# quadcopter.net
KiCad netlist of a schematic drawn in EAGLE
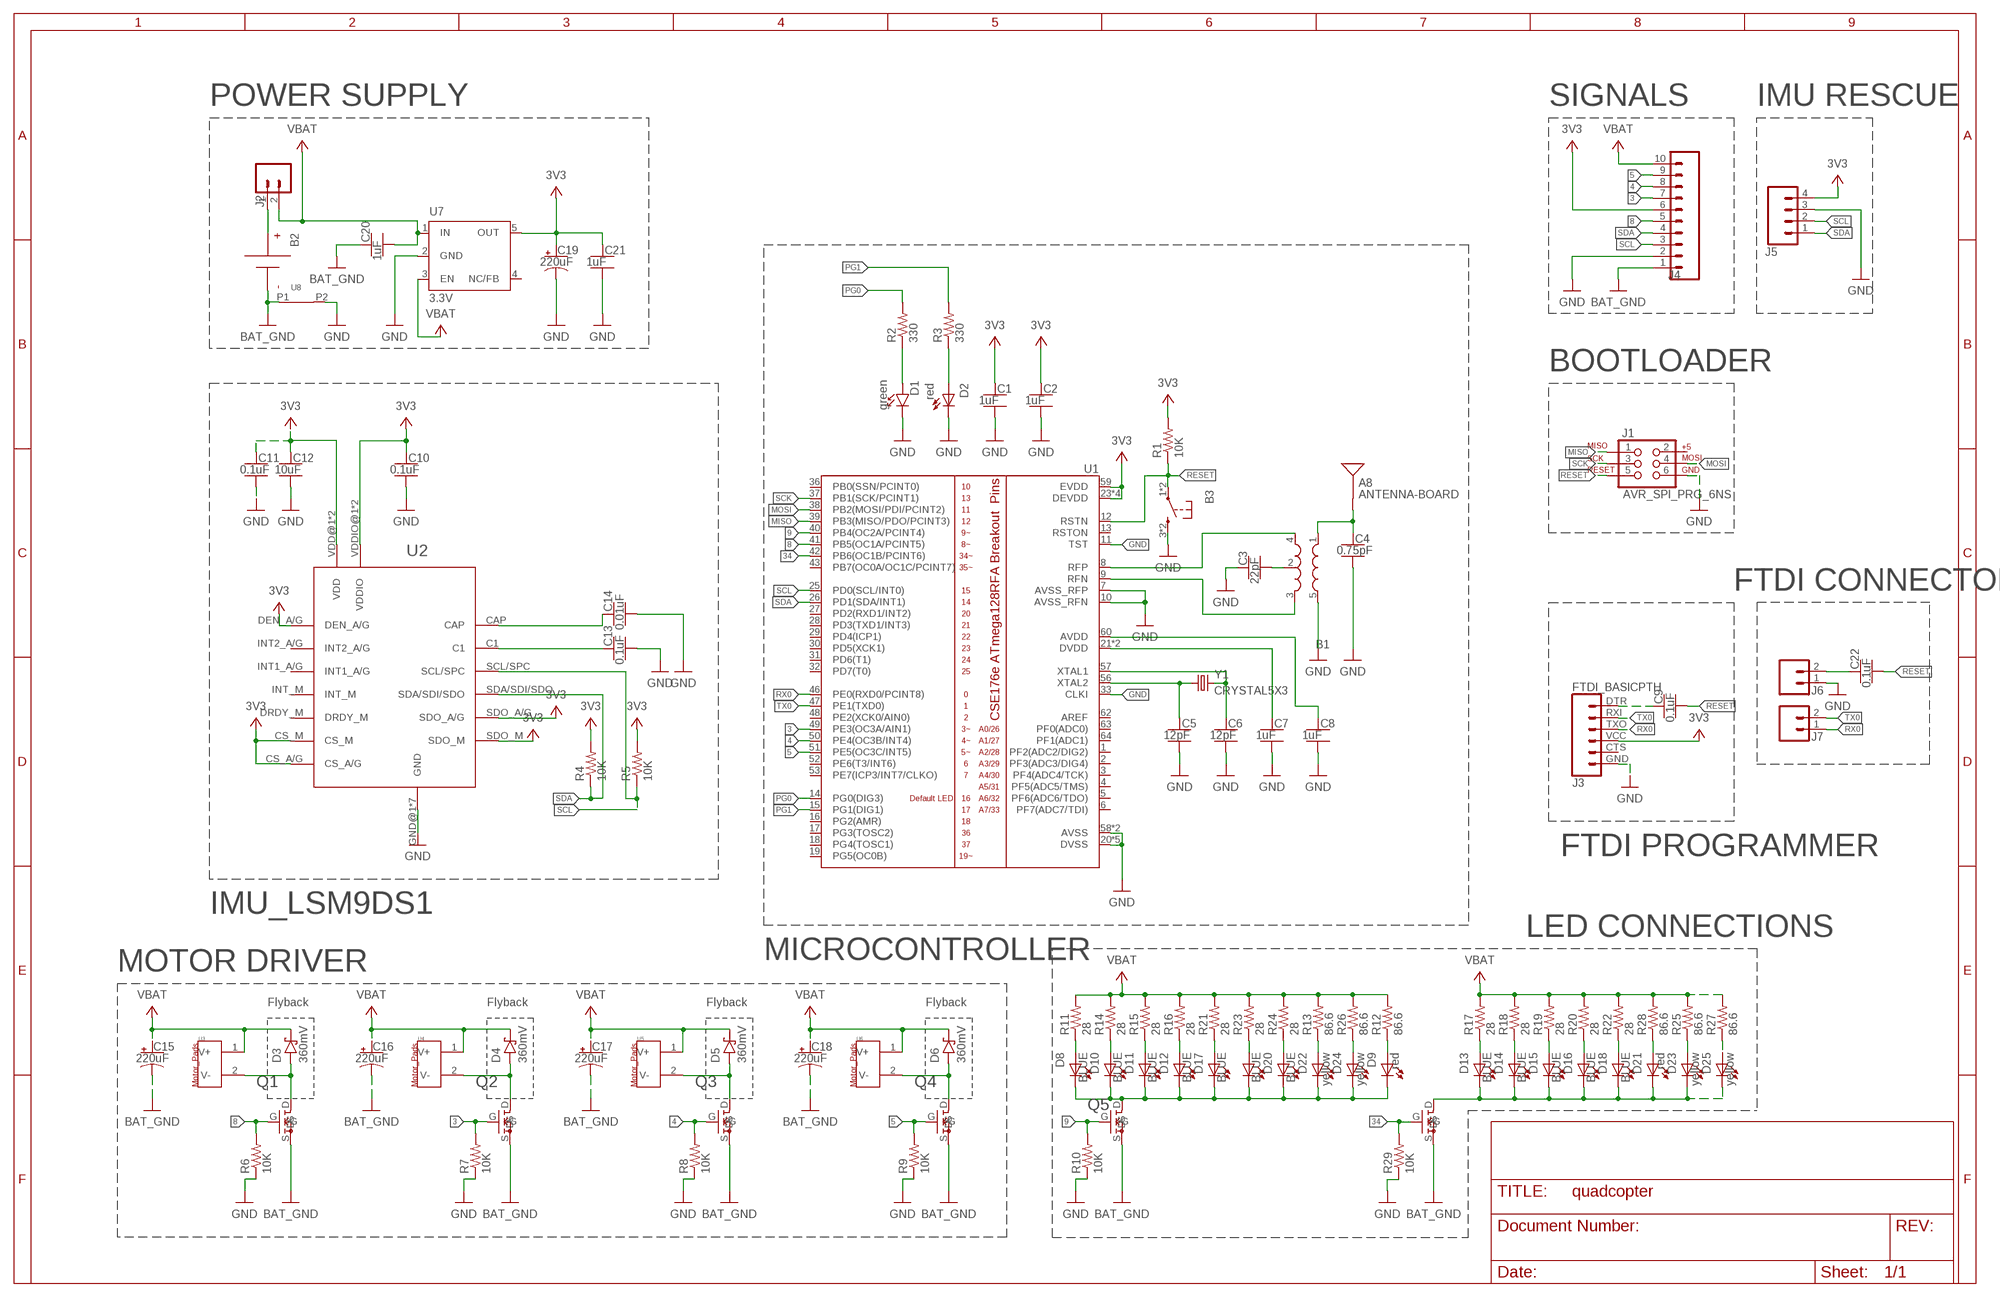
[diagram p0: schematic, sheet 1]

(export (version "E")
  (design (tool "Eeschema 10.0.6"))
  (components
    (comp (ref "A8")
      (value "ANTENNA-BOARD")
      (footprint "eagle-import:ANT_PCB_2.4GHZ_NRF8001_1.6MM_1OZ")
      (libsource (lib "eagle-import") (part "ANTENNA-BOARD"))
    )
    (comp (ref "B1")
      (value "BALUN0805")
      (footprint "eagle-import:BALUN")
      (fields (field (name "MFR") "Wurth Electronics Inc") (field (name "MPN") "748421245"))
      (libsource (lib "eagle-import") (part "BALUN0805"))
    )
    (comp (ref "B2")
      (value "BATTERY-SCREW-TERMINAL")
      (footprint "eagle-import:SCREW-TERMINAL-1X2-2.54MM")
      (libsource (lib "eagle-import") (part "BATTERY-SCREW-TERMINAL"))
    )
    (comp (ref "B3")
      (value "PUSHBUTTON_-4.5X4.5")
      (footprint "eagle-import:4.5MM_TACTILE_SWITCH_TL3305AF160QG")
      (libsource (lib "eagle-import") (part "PUSHBUTTON_-4.5X4.5"))
    )
    (comp (ref "C1")
      (value "1uF")
      (footprint "eagle-import:CAPC2012X140_HS")
      (fields (field (name "MFR") "Taiyo Yuden") (field (name "MPN") "TMK212B7105KG-T"))
      (libsource (lib "eagle-import") (part "CAPACITOR-NP_SMD-2012-0805_CERAMIC-1UF"))
    )
    (comp (ref "C2")
      (value "1uF")
      (footprint "eagle-import:CAPC2012X140_HS")
      (fields (field (name "MFR") "Taiyo Yuden") (field (name "MPN") "TMK212B7105KG-T"))
      (libsource (lib "eagle-import") (part "CAPACITOR-NP_SMD-2012-0805_CERAMIC-1UF"))
    )
    (comp (ref "C3")
      (value "22pF")
      (footprint "eagle-import:CAPC2012X140_HS")
      (fields
        (field (name "MFR") "Murata Electronics North America")
        (field (name "MPN") "GRM21A5C2E220JW01D")
      )
      (libsource (lib "eagle-import") (part "CAPACITOR-NP_SMD-2012-0805_CERAMIC-22PF"))
    )
    (comp (ref "C4")
      (value "0.75pF")
      (footprint "eagle-import:CAPC2012X140_HS")
      (fields
        (field (name "MFR") "Murata Electronics North America")
        (field (name "MPN") "GQM2195C2AR75CB01D")
      )
      (libsource (lib "eagle-import") (part "CAPACITOR-NP_SMD-2012-0805_CERAMIC-0.75PF"))
    )
    (comp (ref "C5")
      (value "12pF")
      (footprint "eagle-import:CAPC2012X140_HS")
      (fields
        (field (name "MFR") "Murata Electronics North America")
        (field (name "MPN") "GRM21A5C2E120JW01D")
      )
      (libsource (lib "eagle-import") (part "CAPACITOR-NP_SMD-2012-0805_CERAMIC-12PF"))
    )
    (comp (ref "C6")
      (value "12pF")
      (footprint "eagle-import:CAPC2012X140_HS")
      (fields
        (field (name "MFR") "Murata Electronics North America")
        (field (name "MPN") "GRM21A5C2E120JW01D")
      )
      (libsource (lib "eagle-import") (part "CAPACITOR-NP_SMD-2012-0805_CERAMIC-12PF"))
    )
    (comp (ref "C7")
      (value "1uF")
      (footprint "eagle-import:CAPC2012X140_HS")
      (fields (field (name "MFR") "Taiyo Yuden") (field (name "MPN") "TMK212B7105KG-T"))
      (libsource (lib "eagle-import") (part "CAPACITOR-NP_SMD-2012-0805_CERAMIC-1UF"))
    )
    (comp (ref "C8")
      (value "1uF")
      (footprint "eagle-import:CAPC2012X140_HS")
      (fields (field (name "MFR") "Taiyo Yuden") (field (name "MPN") "TMK212B7105KG-T"))
      (libsource (lib "eagle-import") (part "CAPACITOR-NP_SMD-2012-0805_CERAMIC-1UF"))
    )
    (comp (ref "C9")
      (value "0.1uF")
      (footprint "eagle-import:CAPC2012X140_HS")
      (fields (field (name "MFR") "TDK") (field (name "MPN") "C2012X7R2A104K125AA"))
      (libsource (lib "eagle-import") (part "CAPACITOR-NP_SMD-2012-0805_CERAMIC-0.1UF"))
    )
    (comp (ref "C10")
      (value "0.1uF")
      (footprint "eagle-import:CAPC2012X140_HS")
      (fields (field (name "MFR") "TDK") (field (name "MPN") "C2012X7R2A104K125AA"))
      (libsource (lib "eagle-import") (part "CAPACITOR-NP_SMD-2012-0805_CERAMIC-0.1UF"))
    )
    (comp (ref "C11")
      (value "0.1uF")
      (footprint "eagle-import:CAPC2012X140_HS")
      (fields (field (name "MFR") "TDK") (field (name "MPN") "C2012X7R2A104K125AA"))
      (libsource (lib "eagle-import") (part "CAPACITOR-NP_SMD-2012-0805_CERAMIC-0.1UF"))
    )
    (comp (ref "C12")
      (value "10uF")
      (footprint "eagle-import:CAPC2012X140_HS")
      (libsource (lib "eagle-import") (part "CAPACITOR-NP_SMD-2012-0805_CERAMIC-10UF"))
    )
    (comp (ref "C13")
      (value "0.1uF")
      (footprint "eagle-import:CAPC2012X140_HS")
      (fields (field (name "MFR") "TDK") (field (name "MPN") "C2012X7R2A104K125AA"))
      (libsource (lib "eagle-import") (part "CAPACITOR-NP_SMD-2012-0805_CERAMIC-0.1UF"))
    )
    (comp (ref "C14")
      (value "0.01uF")
      (footprint "eagle-import:CAPC2012X140_HS")
      (fields (field (name "MFR") "Knowles Syfer") (field (name "MPN") "0805J0500104KJT"))
      (libsource (lib "eagle-import") (part "CAPACITOR-NP_SMD-2012-0805_CERAMIC-0.01UF"))
    )
    (comp (ref "C15")
      (value "220uF")
      (footprint "eagle-import:CAPMP7343X310_HS")
      (fields (field (name "MFR") "AVX Corporation") (field (name "MPN") "TAJD227K006RNJ"))
      (libsource (lib "eagle-import") (part "CAPACITOR-POL_SMD-7043-D_TANTALUM-220UF"))
    )
    (comp (ref "C16")
      (value "220uF")
      (footprint "eagle-import:CAPMP7343X310_HS")
      (fields (field (name "MFR") "AVX Corporation") (field (name "MPN") "TAJD227K006RNJ"))
      (libsource (lib "eagle-import") (part "CAPACITOR-POL_SMD-7043-D_TANTALUM-220UF"))
    )
    (comp (ref "C17")
      (value "220uF")
      (footprint "eagle-import:CAPMP7343X310_HS")
      (fields (field (name "MFR") "AVX Corporation") (field (name "MPN") "TAJD227K006RNJ"))
      (libsource (lib "eagle-import") (part "CAPACITOR-POL_SMD-7043-D_TANTALUM-220UF"))
    )
    (comp (ref "C18")
      (value "220uF")
      (footprint "eagle-import:CAPMP7343X310_HS")
      (fields (field (name "MFR") "AVX Corporation") (field (name "MPN") "TAJD227K006RNJ"))
      (libsource (lib "eagle-import") (part "CAPACITOR-POL_SMD-7043-D_TANTALUM-220UF"))
    )
    (comp (ref "C19")
      (value "220uF")
      (footprint "eagle-import:CAPMP7343X310_HS")
      (fields (field (name "MFR") "AVX Corporation") (field (name "MPN") "TAJD227K006RNJ"))
      (libsource (lib "eagle-import") (part "CAPACITOR-POL_SMD-7043-D_TANTALUM-220UF"))
    )
    (comp (ref "C20")
      (value "1uF")
      (footprint "eagle-import:CAPC2012X140_HS")
      (fields (field (name "MFR") "Taiyo Yuden") (field (name "MPN") "TMK212B7105KG-T"))
      (libsource (lib "eagle-import") (part "CAPACITOR-NP_SMD-2012-0805_CERAMIC-1UF"))
    )
    (comp (ref "C21")
      (value "1uF")
      (footprint "eagle-import:CAPC2012X140_HS")
      (fields (field (name "MFR") "Taiyo Yuden") (field (name "MPN") "TMK212B7105KG-T"))
      (libsource (lib "eagle-import") (part "CAPACITOR-NP_SMD-2012-0805_CERAMIC-1UF"))
    )
    (comp (ref "C22")
      (value "0.1uF")
      (footprint "eagle-import:CAPC2012X140_HS")
      (fields (field (name "MFR") "TDK") (field (name "MPN") "C2012X7R2A104K125AA"))
      (libsource (lib "eagle-import") (part "CAPACITOR-NP_SMD-2012-0805_CERAMIC-0.1UF"))
    )
    (comp (ref "D1")
      (value "green")
      (footprint "eagle-import:LEDSC125X200X120-2_HS")
      (fields (field (name "MFR") "Lite-On Inc") (field (name "MPN") "LTST-C170GKT"))
      (libsource (lib "eagle-import") (part "DIODE-LED_SMD-2012-0805-GREEN"))
    )
    (comp (ref "D2")
      (value "red")
      (footprint "eagle-import:LED")
      (libsource (lib "eagle-import") (part "DIODE-LED-LITEON-C170EKT-RED-LITEON-C170EKT-RED-LED"))
    )
    (comp (ref "D3")
      (value "360mV")
      (footprint "eagle-import:SOD3716X135_HS")
      (fields
        (field (name "MFR") "Toshiba Semiconductor and Storage")
        (field (name "MPN") "CRS08(TE85L,Q,M)")
      )
      (libsource (lib "eagle-import") (part "DIODE-SCHOTTKY_SMD-SOD123-360MV"))
    )
    (comp (ref "D4")
      (value "360mV")
      (footprint "eagle-import:SOD3716X135_HS")
      (fields
        (field (name "MFR") "Toshiba Semiconductor and Storage")
        (field (name "MPN") "CRS08(TE85L,Q,M)")
      )
      (libsource (lib "eagle-import") (part "DIODE-SCHOTTKY_SMD-SOD123-360MV"))
    )
    (comp (ref "D5")
      (value "360mV")
      (footprint "eagle-import:SOD3716X135_HS")
      (fields
        (field (name "MFR") "Toshiba Semiconductor and Storage")
        (field (name "MPN") "CRS08(TE85L,Q,M)")
      )
      (libsource (lib "eagle-import") (part "DIODE-SCHOTTKY_SMD-SOD123-360MV"))
    )
    (comp (ref "D6")
      (value "360mV")
      (footprint "eagle-import:SOD3716X135_HS")
      (fields
        (field (name "MFR") "Toshiba Semiconductor and Storage")
        (field (name "MPN") "CRS08(TE85L,Q,M)")
      )
      (libsource (lib "eagle-import") (part "DIODE-SCHOTTKY_SMD-SOD123-360MV"))
    )
    (comp (ref "D8")
      (value "BLUE")
      (footprint "eagle-import:DIODE-LED-LTST-C170")
      (fields (field (name "MFR") "Lite-On Inc") (field (name "MPN") "LTST-C170TBKT"))
      (libsource (lib "eagle-import") (part "DIODE-LED-SMD-2012-0805-BLUE-BLUE"))
    )
    (comp (ref "D9")
      (value "red")
      (footprint "eagle-import:DIODE-LED-LTST-C170")
      (fields (field (name "MFR") "Lite-on Inc") (field (name "MPN") "LTST-C170KRKT"))
      (libsource (lib "eagle-import") (part "DIODE-LED-SMD-2012-0805-RED-RED"))
    )
    (comp (ref "D10")
      (value "BLUE")
      (footprint "eagle-import:DIODE-LED-LTST-C170")
      (fields (field (name "MFR") "Lite-On Inc") (field (name "MPN") "LTST-C170TBKT"))
      (libsource (lib "eagle-import") (part "DIODE-LED-SMD-2012-0805-BLUE-BLUE"))
    )
    (comp (ref "D11")
      (value "BLUE")
      (footprint "eagle-import:DIODE-LED-LTST-C170")
      (fields (field (name "MFR") "Lite-On Inc") (field (name "MPN") "LTST-C170TBKT"))
      (libsource (lib "eagle-import") (part "DIODE-LED-SMD-2012-0805-BLUE-BLUE"))
    )
    (comp (ref "D12")
      (value "BLUE")
      (footprint "eagle-import:DIODE-LED-LTST-C170")
      (fields (field (name "MFR") "Lite-On Inc") (field (name "MPN") "LTST-C170TBKT"))
      (libsource (lib "eagle-import") (part "DIODE-LED-SMD-2012-0805-BLUE-BLUE"))
    )
    (comp (ref "D13")
      (value "BLUE")
      (footprint "eagle-import:DIODE-LED-LTST-C170")
      (fields (field (name "MFR") "Lite-On Inc") (field (name "MPN") "LTST-C170TBKT"))
      (libsource (lib "eagle-import") (part "DIODE-LED-SMD-2012-0805-BLUE-BLUE"))
    )
    (comp (ref "D14")
      (value "BLUE")
      (footprint "eagle-import:DIODE-LED-LTST-C170")
      (fields (field (name "MFR") "Lite-On Inc") (field (name "MPN") "LTST-C170TBKT"))
      (libsource (lib "eagle-import") (part "DIODE-LED-SMD-2012-0805-BLUE-BLUE"))
    )
    (comp (ref "D15")
      (value "BLUE")
      (footprint "eagle-import:DIODE-LED-LTST-C170")
      (fields (field (name "MFR") "Lite-On Inc") (field (name "MPN") "LTST-C170TBKT"))
      (libsource (lib "eagle-import") (part "DIODE-LED-SMD-2012-0805-BLUE-BLUE"))
    )
    (comp (ref "D16")
      (value "BLUE")
      (footprint "eagle-import:DIODE-LED-LTST-C170")
      (fields (field (name "MFR") "Lite-On Inc") (field (name "MPN") "LTST-C170TBKT"))
      (libsource (lib "eagle-import") (part "DIODE-LED-SMD-2012-0805-BLUE-BLUE"))
    )
    (comp (ref "D17")
      (value "BLUE")
      (footprint "eagle-import:DIODE-LED-LTST-C170")
      (fields (field (name "MFR") "Lite-On Inc") (field (name "MPN") "LTST-C170TBKT"))
      (libsource (lib "eagle-import") (part "DIODE-LED-SMD-2012-0805-BLUE-BLUE"))
    )
    (comp (ref "D18")
      (value "BLUE")
      (footprint "eagle-import:DIODE-LED-LTST-C170")
      (fields (field (name "MFR") "Lite-On Inc") (field (name "MPN") "LTST-C170TBKT"))
      (libsource (lib "eagle-import") (part "DIODE-LED-SMD-2012-0805-BLUE-BLUE"))
    )
    (comp (ref "D19")
      (value "BLUE")
      (footprint "eagle-import:DIODE-LED-LTST-C170")
      (fields (field (name "MFR") "Lite-On Inc") (field (name "MPN") "LTST-C170TBKT"))
      (libsource (lib "eagle-import") (part "DIODE-LED-SMD-2012-0805-BLUE-BLUE"))
    )
    (comp (ref "D20")
      (value "BLUE")
      (footprint "eagle-import:DIODE-LED-LTST-C170")
      (fields (field (name "MFR") "Lite-On Inc") (field (name "MPN") "LTST-C170TBKT"))
      (libsource (lib "eagle-import") (part "DIODE-LED-SMD-2012-0805-BLUE-BLUE"))
    )
    (comp (ref "D21")
      (value "red")
      (footprint "eagle-import:DIODE-LED-LTST-C170")
      (fields (field (name "MFR") "Lite-on Inc") (field (name "MPN") "LTST-C170KRKT"))
      (libsource (lib "eagle-import") (part "DIODE-LED-SMD-2012-0805-RED-RED"))
    )
    (comp (ref "D22")
      (value "yellow")
      (footprint "eagle-import:DIODE-LED-LTST-C170")
      (fields (field (name "MFR") "Lite-On Inc") (field (name "MPN") "LTST-C170KSKT"))
      (libsource (lib "eagle-import") (part "DIODE-LED-SMD-2012-0805-YELLOW-YELLOW"))
    )
    (comp (ref "D23")
      (value "yellow")
      (footprint "eagle-import:DIODE-LED-LTST-C170")
      (fields (field (name "MFR") "Lite-On Inc") (field (name "MPN") "LTST-C170KSKT"))
      (libsource (lib "eagle-import") (part "DIODE-LED-SMD-2012-0805-YELLOW-YELLOW"))
    )
    (comp (ref "D24")
      (value "yellow")
      (footprint "eagle-import:DIODE-LED-LTST-C170")
      (fields (field (name "MFR") "Lite-On Inc") (field (name "MPN") "LTST-C170KSKT"))
      (libsource (lib "eagle-import") (part "DIODE-LED-SMD-2012-0805-YELLOW-YELLOW"))
    )
    (comp (ref "D25")
      (value "yellow")
      (footprint "eagle-import:DIODE-LED-LTST-C170")
      (fields (field (name "MFR") "Lite-On Inc") (field (name "MPN") "LTST-C170KSKT"))
      (libsource (lib "eagle-import") (part "DIODE-LED-SMD-2012-0805-YELLOW-YELLOW"))
    )
    (comp (ref "J1")
      (value "AVR_SPI_PRG_6NS")
      (footprint "eagle-import:2X3-NS")
      (fields (field (name "MFR") "Amphenol FCI") (field (name "MPN") "67997-206HLF"))
      (libsource (lib "eagle-import") (part "AVR_SPI_PRG_6NS"))
    )
    (comp (ref "J2")
      (value "HEADER-0.1IN-2POS-MALE")
      (footprint "eagle-import:HDRV2W63P254_2X1_508X254H838_HS")
      (libsource (lib "eagle-import") (part "HEADER-0.1IN-2POS-MALE"))
    )
    (comp (ref "J3")
      (value "FTDI_BASICPTH")
      (footprint "eagle-import:FTDI_BASIC")
      (fields (field (name "MFR") "Amphenol FCI") (field (name "MPN") "68016-406HLF"))
      (libsource (lib "eagle-import") (part "FTDI_BASICPTH"))
    )
    (comp (ref "J4")
      (value "HEADER-10POSTH-254X10")
      (footprint "eagle-import:HDRV10W63P254_10X1_2540X254H838_HS")
      (fields (field (name "MFR") "Amphenol FCI") (field (name "MPN") "68000-110HLF"))
      (libsource (lib "eagle-import") (part "HEADER-10POSTH-254X10"))
    )
    (comp (ref "J5")
      (value "HEADER-4POS-0.1IN-FEMALE")
      (footprint "eagle-import:HDRVR4W80P254_1X4_1066X254X850B")
      (libsource (lib "eagle-import") (part "HEADER-4POS-0.1IN-FEMALE"))
    )
    (comp (ref "J6")
      (value "HEADER-0.1IN-2POS-FEMALE")
      (footprint "eagle-import:HDRV2W63P254_2X1_508X254H838_HS")
      (libsource (lib "eagle-import") (part "HEADER-0.1IN-2POS-FEMALE"))
    )
    (comp (ref "J7")
      (value "HEADER-0.1IN-2POS-FEMALE")
      (footprint "eagle-import:HDRV2W63P254_2X1_508X254H838_HS")
      (libsource (lib "eagle-import") (part "HEADER-0.1IN-2POS-FEMALE"))
    )
    (comp (ref "Q1")
      (value "MOSFET-VISHAY-SOT23-N-MOSFET")
      (footprint "eagle-import:SOT-23_N_MOSFET")
      (libsource (lib "eagle-import") (part "MOSFET-VISHAY-SOT23-N-MOSFET"))
    )
    (comp (ref "Q2")
      (value "MOSFET-VISHAY-SOT23-N-MOSFET")
      (footprint "eagle-import:SOT-23_N_MOSFET")
      (libsource (lib "eagle-import") (part "MOSFET-VISHAY-SOT23-N-MOSFET"))
    )
    (comp (ref "Q3")
      (value "MOSFET-VISHAY-SOT23-N-MOSFET")
      (footprint "eagle-import:SOT-23_N_MOSFET")
      (libsource (lib "eagle-import") (part "MOSFET-VISHAY-SOT23-N-MOSFET"))
    )
    (comp (ref "Q4")
      (value "MOSFET-VISHAY-SOT23-N-MOSFET")
      (footprint "eagle-import:SOT-23_N_MOSFET")
      (libsource (lib "eagle-import") (part "MOSFET-VISHAY-SOT23-N-MOSFET"))
    )
    (comp (ref "Q5")
      (value "MOSFET-VISHAY-SOT23-N-MOSFET")
      (footprint "eagle-import:SOT-23_N_MOSFET")
      (libsource (lib "eagle-import") (part "MOSFET-VISHAY-SOT23-N-MOSFET"))
    )
    (comp (ref "Q6")
      (value "MOSFET-VISHAY-SOT23-N-MOSFET")
      (footprint "eagle-import:SOT-23_N_MOSFET")
      (libsource (lib "eagle-import") (part "MOSFET-VISHAY-SOT23-N-MOSFET"))
    )
    (comp (ref "R1")
      (value "10K")
      (footprint "eagle-import:RESC2012X60_HS")
      (fields (field (name "MFR") "Yageo") (field (name "MPN") "RC0805JR-0710KL"))
      (libsource (lib "eagle-import") (part "quadparts_prebuilt_RESISTOR_SMD-2012-0805-10K"))
    )
    (comp (ref "R2")
      (value "330")
      (footprint "eagle-import:RESC2012X60_HS")
      (fields (field (name "MFR") "Yageo") (field (name "MPN") "RC0805JR-07330RL"))
      (libsource (lib "eagle-import") (part "quadparts_prebuilt_RESISTOR_SMD-2012-0805-330"))
    )
    (comp (ref "R3")
      (value "330")
      (footprint "eagle-import:RESC2012X60_HS")
      (fields (field (name "MFR") "Yageo") (field (name "MPN") "RC0805JR-07330RL"))
      (libsource (lib "eagle-import") (part "quadparts_prebuilt_RESISTOR_SMD-2012-0805-330"))
    )
    (comp (ref "R4")
      (value "10K")
      (footprint "eagle-import:RESC2012X60_HS")
      (fields (field (name "MFR") "Yageo") (field (name "MPN") "RC0805JR-0710KL"))
      (libsource (lib "eagle-import") (part "quadparts_prebuilt_RESISTOR_SMD-2012-0805-10K"))
    )
    (comp (ref "R5")
      (value "10K")
      (footprint "eagle-import:RESC2012X60_HS")
      (fields (field (name "MFR") "Yageo") (field (name "MPN") "RC0805JR-0710KL"))
      (libsource (lib "eagle-import") (part "quadparts_prebuilt_RESISTOR_SMD-2012-0805-10K"))
    )
    (comp (ref "R6")
      (value "10K")
      (footprint "eagle-import:RESC2012X60_HS")
      (fields (field (name "MFR") "Yageo") (field (name "MPN") "RC0805JR-0710KL"))
      (libsource (lib "eagle-import") (part "quadparts_prebuilt_RESISTOR_SMD-2012-0805-10K"))
    )
    (comp (ref "R7")
      (value "10K")
      (footprint "eagle-import:RESC2012X60_HS")
      (fields (field (name "MFR") "Yageo") (field (name "MPN") "RC0805JR-0710KL"))
      (libsource (lib "eagle-import") (part "quadparts_prebuilt_RESISTOR_SMD-2012-0805-10K"))
    )
    (comp (ref "R8")
      (value "10K")
      (footprint "eagle-import:RESC2012X60_HS")
      (fields (field (name "MFR") "Yageo") (field (name "MPN") "RC0805JR-0710KL"))
      (libsource (lib "eagle-import") (part "quadparts_prebuilt_RESISTOR_SMD-2012-0805-10K"))
    )
    (comp (ref "R9")
      (value "10K")
      (footprint "eagle-import:RESC2012X60_HS")
      (fields (field (name "MFR") "Yageo") (field (name "MPN") "RC0805JR-0710KL"))
      (libsource (lib "eagle-import") (part "quadparts_prebuilt_RESISTOR_SMD-2012-0805-10K"))
    )
    (comp (ref "R10")
      (value "10K")
      (footprint "eagle-import:RESC2012X60_HS")
      (fields (field (name "MFR") "Yageo") (field (name "MPN") "RC0805JR-0710KL"))
      (libsource (lib "eagle-import") (part "quadparts_prebuilt_RESISTOR_SMD-2012-0805-10K"))
    )
    (comp (ref "R11")
      (value "28")
      (footprint "eagle-import:RESC2012X60_HS")
      (libsource (lib "eagle-import") (part "RESISTOR_SMD-2012-0805-28"))
    )
    (comp (ref "R12")
      (value "86.6")
      (footprint "eagle-import:RESC2012X60_HS")
      (libsource (lib "eagle-import") (part "RESISTOR_SMD-2012-0805-88.6"))
    )
    (comp (ref "R13")
      (value "86.6")
      (footprint "eagle-import:RESC2012X60_HS")
      (libsource (lib "eagle-import") (part "RESISTOR_SMD-2012-0805-88.6"))
    )
    (comp (ref "R14")
      (value "28")
      (footprint "eagle-import:RESC2012X60_HS")
      (libsource (lib "eagle-import") (part "RESISTOR_SMD-2012-0805-28"))
    )
    (comp (ref "R15")
      (value "28")
      (footprint "eagle-import:RESC2012X60_HS")
      (libsource (lib "eagle-import") (part "RESISTOR_SMD-2012-0805-28"))
    )
    (comp (ref "R16")
      (value "28")
      (footprint "eagle-import:RESC2012X60_HS")
      (libsource (lib "eagle-import") (part "RESISTOR_SMD-2012-0805-28"))
    )
    (comp (ref "R17")
      (value "28")
      (footprint "eagle-import:RESC2012X60_HS")
      (libsource (lib "eagle-import") (part "RESISTOR_SMD-2012-0805-28"))
    )
    (comp (ref "R18")
      (value "28")
      (footprint "eagle-import:RESC2012X60_HS")
      (libsource (lib "eagle-import") (part "RESISTOR_SMD-2012-0805-28"))
    )
    (comp (ref "R19")
      (value "28")
      (footprint "eagle-import:RESC2012X60_HS")
      (libsource (lib "eagle-import") (part "RESISTOR_SMD-2012-0805-28"))
    )
    (comp (ref "R20")
      (value "28")
      (footprint "eagle-import:RESC2012X60_HS")
      (libsource (lib "eagle-import") (part "RESISTOR_SMD-2012-0805-28"))
    )
    (comp (ref "R21")
      (value "28")
      (footprint "eagle-import:RESC2012X60_HS")
      (libsource (lib "eagle-import") (part "RESISTOR_SMD-2012-0805-28"))
    )
    (comp (ref "R22")
      (value "28")
      (footprint "eagle-import:RESC2012X60_HS")
      (libsource (lib "eagle-import") (part "RESISTOR_SMD-2012-0805-28"))
    )
    (comp (ref "R23")
      (value "28")
      (footprint "eagle-import:RESC2012X60_HS")
      (libsource (lib "eagle-import") (part "RESISTOR_SMD-2012-0805-28"))
    )
    (comp (ref "R24")
      (value "28")
      (footprint "eagle-import:RESC2012X60_HS")
      (libsource (lib "eagle-import") (part "RESISTOR_SMD-2012-0805-28"))
    )
    (comp (ref "R25")
      (value "86.6")
      (footprint "eagle-import:RESC2012X60_HS")
      (libsource (lib "eagle-import") (part "RESISTOR_SMD-2012-0805-88.6"))
    )
    (comp (ref "R26")
      (value "86.6")
      (footprint "eagle-import:RESC2012X60_HS")
      (libsource (lib "eagle-import") (part "RESISTOR_SMD-2012-0805-88.6"))
    )
    (comp (ref "R27")
      (value "86.6")
      (footprint "eagle-import:RESC2012X60_HS")
      (libsource (lib "eagle-import") (part "RESISTOR_SMD-2012-0805-88.6"))
    )
    (comp (ref "R28")
      (value "86.6")
      (footprint "eagle-import:RESC2012X60_HS")
      (libsource (lib "eagle-import") (part "RESISTOR_SMD-2012-0805-88.6"))
    )
    (comp (ref "R29")
      (value "10K")
      (footprint "eagle-import:RESC2012X60_HS")
      (fields (field (name "MFR") "Yageo") (field (name "MPN") "RC0805JR-0710KL"))
      (libsource (lib "eagle-import") (part "quadparts_prebuilt_RESISTOR_SMD-2012-0805-10K"))
    )
    (comp (ref "U1")
      (value "ATMEGA128RFA1")
      (footprint "eagle-import:QFN-64")
      (fields (field (name "MFR") "Atmel") (field (name "MPN") "ATMEGA128RFA1-ZUR00"))
      (libsource (lib "eagle-import") (part "ATMEGA128RFA1"))
    )
    (comp (ref "U2")
      (value "IMU_LSM-ST-LSM9DS1-IMU-LGA")
      (footprint "eagle-import:LSM9DS1_IMU")
      (libsource (lib "eagle-import") (part "IMU_LSM-ST-LSM9DS1-IMU-LGA"))
    )
    (comp (ref "U3")
      (value "MOTOR_PADS-MOLEX-0530470210")
      (footprint "eagle-import:MOLEX-0530470210")
      (libsource (lib "eagle-import") (part "MOTOR_PADS-MOLEX-0530470210"))
    )
    (comp (ref "U4")
      (value "MOTOR_PADS-MOLEX-0530470210")
      (footprint "eagle-import:MOLEX-0530470210")
      (libsource (lib "eagle-import") (part "MOTOR_PADS-MOLEX-0530470210"))
    )
    (comp (ref "U5")
      (value "MOTOR_PADS-MOLEX-0530470210")
      (footprint "eagle-import:MOLEX-0530470210")
      (libsource (lib "eagle-import") (part "MOTOR_PADS-MOLEX-0530470210"))
    )
    (comp (ref "U6")
      (value "MOTOR_PADS-MOLEX-0530470210")
      (footprint "eagle-import:MOLEX-0530470210")
      (libsource (lib "eagle-import") (part "MOTOR_PADS-MOLEX-0530470210"))
    )
    (comp (ref "U7")
      (value "3.3V")
      (footprint "eagle-import:SOT23-DBV")
      (libsource (lib "eagle-import") (part "TPS73633-DBVT3V3"))
    )
    (comp (ref "U8")
      (value "NET_BRIDGE-BRIDGE-SMD")
      (footprint "eagle-import:NET_BRIDGE")
      (libsource (lib "eagle-import") (part "NET_BRIDGE-BRIDGE-SMD"))
    )
    (comp (ref "Y1")
      (value "CRYSTAL5X3")
      (footprint "eagle-import:CRYSTAL-SMD-5X3")
      (fields (field (name "MFR") "Abracon LLC") (field (name "MPN") "ABM3B-16.000MHZ-B2-T"))
      (libsource (lib "eagle-import") (part "CRYSTAL5X3"))
    )
  )
  (nets
    (net (code "1") (name "3") (class "Default")
      (node (ref "J4") (pin "7") (pinfunction "7_7") (pintype "passive"))
      (node (ref "Q2") (pin "G") (pinfunction "G_G") (pintype "bidirectional"))
      (node (ref "R7") (pin "2") (pinfunction "2_2") (pintype "passive"))
      (node (ref "U1") (pin "49") (pinfunction "PE3(OC3A/AIN1)_49") (pintype "bidirectional"))
    )
    (net (code "2") (name "3V3") (class "Default")
      (node (ref "C1") (pin "1") (pinfunction "1_1") (pintype "passive"))
      (node (ref "C10") (pin "1") (pinfunction "1_1") (pintype "passive"))
      (node (ref "C11") (pin "1") (pinfunction "1_1") (pintype "passive"))
      (node (ref "C12") (pin "1") (pinfunction "1_1") (pintype "passive"))
      (node (ref "C19") (pin "1") (pinfunction "+_1") (pintype "passive"))
      (node (ref "C2") (pin "1") (pinfunction "1_1") (pintype "passive"))
      (node (ref "C21") (pin "1") (pinfunction "1_1") (pintype "passive"))
      (node (ref "J3") (pin "VCC") (pinfunction "4_VCC") (pintype "passive"))
      (node (ref "J4") (pin "6") (pinfunction "6_6") (pintype "passive"))
      (node (ref "J5") (pin "4") (pinfunction "4_4") (pintype "bidirectional"))
      (node (ref "R1") (pin "2") (pinfunction "2_2") (pintype "passive"))
      (node (ref "R4") (pin "2") (pinfunction "2_2") (pintype "passive"))
      (node (ref "R5") (pin "2") (pinfunction "2_2") (pintype "passive"))
      (node (ref "U1") (pin "23") (pinfunction "DEVDD_23") (pintype "bidirectional"))
      (node (ref "U1") (pin "34") (pinfunction "DEVDD_34") (pintype "bidirectional"))
      (node (ref "U1") (pin "44") (pinfunction "DEVDD_44") (pintype "bidirectional"))
      (node (ref "U1") (pin "54") (pinfunction "DEVDD_54") (pintype "bidirectional"))
      (node (ref "U1") (pin "59") (pinfunction "EVDD_59") (pintype "bidirectional"))
      (node (ref "U2") (pin "CS_A/G") (pinfunction "CS_A/G_CS_A/G") (pintype "bidirectional"))
      (node (ref "U2") (pin "CS_M") (pinfunction "CS_M_CS_M") (pintype "bidirectional"))
      (node (ref "U2") (pin "DEN_A/G") (pinfunction "DEN_A/G_DEN_A/G") (pintype "bidirectional"))
      (node (ref "U2") (pin "SDO_A/G") (pinfunction "SDO_A/G_SDO_A/G") (pintype "bidirectional"))
      (node (ref "U2") (pin "SDO_M") (pinfunction "SDO_M_SDO_M") (pintype "bidirectional"))
      (node (ref "U2") (pin "VDD@1") (pinfunction "VDD_VDD@1") (pintype "bidirectional"))
      (node (ref "U2") (pin "VDD@2") (pinfunction "VDD_VDD@2") (pintype "bidirectional"))
      (node (ref "U2") (pin "VDDIO@1") (pinfunction "VDDIO_VDDIO@1") (pintype "bidirectional"))
      (node (ref "U2") (pin "VDDIO@2") (pinfunction "VDDIO_VDDIO@2") (pintype "bidirectional"))
      (node (ref "U7") (pin "5") (pinfunction "OUT_5") (pintype "passive"))
    )
    (net (code "3") (name "4") (class "Default")
      (node (ref "J4") (pin "8") (pinfunction "8_8") (pintype "passive"))
      (node (ref "Q3") (pin "G") (pinfunction "G_G") (pintype "bidirectional"))
      (node (ref "R8") (pin "2") (pinfunction "2_2") (pintype "passive"))
      (node (ref "U1") (pin "50") (pinfunction "PE4(OC3B/INT4)_50") (pintype "bidirectional"))
    )
    (net (code "4") (name "5") (class "Default")
      (node (ref "J4") (pin "9") (pinfunction "9_9") (pintype "passive"))
      (node (ref "Q4") (pin "G") (pinfunction "G_G") (pintype "bidirectional"))
      (node (ref "R9") (pin "2") (pinfunction "2_2") (pintype "passive"))
      (node (ref "U1") (pin "51") (pinfunction "PE5(OC3C/INT5)_51") (pintype "bidirectional"))
    )
    (net (code "5") (name "8") (class "Default")
      (node (ref "J4") (pin "5") (pinfunction "5_5") (pintype "passive"))
      (node (ref "Q1") (pin "G") (pinfunction "G_G") (pintype "bidirectional"))
      (node (ref "R6") (pin "2") (pinfunction "2_2") (pintype "passive"))
      (node (ref "U1") (pin "41") (pinfunction "PB5(OC1A/PCINT5)_41") (pintype "bidirectional"))
    )
    (net (code "6") (name "9") (class "Default")
      (node (ref "Q5") (pin "G") (pinfunction "G_G") (pintype "bidirectional"))
      (node (ref "R10") (pin "2") (pinfunction "2_2") (pintype "passive"))
      (node (ref "U1") (pin "40") (pinfunction "PB4(OC2A/PCINT4)_40") (pintype "bidirectional"))
    )
    (net (code "7") (name "34") (class "Default")
      (node (ref "Q6") (pin "G") (pinfunction "G_G") (pintype "bidirectional"))
      (node (ref "R29") (pin "2") (pinfunction "2_2") (pintype "passive"))
      (node (ref "U1") (pin "42") (pinfunction "PB6(OC1B/PCINT6)_42") (pintype "bidirectional"))
    )
    (net (code "8") (name "BAT_GND") (class "Default")
      (node (ref "B2") (pin "1") (pinfunction "N_1") (pintype "bidirectional"))
      (node (ref "C15") (pin "2") (pinfunction "-_2") (pintype "passive"))
      (node (ref "C16") (pin "2") (pinfunction "-_2") (pintype "passive"))
      (node (ref "C17") (pin "2") (pinfunction "-_2") (pintype "passive"))
      (node (ref "C18") (pin "2") (pinfunction "-_2") (pintype "passive"))
      (node (ref "C20") (pin "1") (pinfunction "1_1") (pintype "passive"))
      (node (ref "J4") (pin "1") (pinfunction "1_1") (pintype "passive"))
      (node (ref "Q1") (pin "S") (pinfunction "S_S") (pintype "bidirectional"))
      (node (ref "Q2") (pin "S") (pinfunction "S_S") (pintype "bidirectional"))
      (node (ref "Q3") (pin "S") (pinfunction "S_S") (pintype "bidirectional"))
      (node (ref "Q4") (pin "S") (pinfunction "S_S") (pintype "bidirectional"))
      (node (ref "Q5") (pin "S") (pinfunction "S_S") (pintype "bidirectional"))
      (node (ref "Q6") (pin "S") (pinfunction "S_S") (pintype "bidirectional"))
      (node (ref "U8") (pin "P1") (pinfunction "P1_P1") (pintype "bidirectional"))
    )
    (net (code "9") (name "GND") (class "Default")
      (node (ref "B1") (pin "5") (pinfunction "GND_5") (pintype "bidirectional"))
      (node (ref "B3") (pin "3") (pinfunction "2_3") (pintype "passive"))
      (node (ref "B3") (pin "4") (pinfunction "2_4") (pintype "passive"))
      (node (ref "C1") (pin "2") (pinfunction "2_2") (pintype "passive"))
      (node (ref "C10") (pin "2") (pinfunction "2_2") (pintype "passive"))
      (node (ref "C11") (pin "2") (pinfunction "2_2") (pintype "passive"))
      (node (ref "C12") (pin "2") (pinfunction "2_2") (pintype "passive"))
      (node (ref "C13") (pin "2") (pinfunction "2_2") (pintype "passive"))
      (node (ref "C14") (pin "2") (pinfunction "2_2") (pintype "passive"))
      (node (ref "C19") (pin "2") (pinfunction "-_2") (pintype "passive"))
      (node (ref "C2") (pin "2") (pinfunction "2_2") (pintype "passive"))
      (node (ref "C21") (pin "2") (pinfunction "2_2") (pintype "passive"))
      (node (ref "C3") (pin "1") (pinfunction "1_1") (pintype "passive"))
      (node (ref "C4") (pin "2") (pinfunction "2_2") (pintype "passive"))
      (node (ref "C5") (pin "2") (pinfunction "2_2") (pintype "passive"))
      (node (ref "C6") (pin "2") (pinfunction "2_2") (pintype "passive"))
      (node (ref "C7") (pin "2") (pinfunction "2_2") (pintype "passive"))
      (node (ref "C8") (pin "2") (pinfunction "2_2") (pintype "passive"))
      (node (ref "D1") (pin "C") (pinfunction "C_C") (pintype "passive"))
      (node (ref "D2") (pin "C") (pinfunction "C_C") (pintype "passive"))
      (node (ref "J1") (pin "6") (pinfunction "6_6") (pintype "passive"))
      (node (ref "J3") (pin "GND") (pinfunction "6_GND") (pintype "passive"))
      (node (ref "J4") (pin "2") (pinfunction "2_2") (pintype "passive"))
      (node (ref "J5") (pin "3") (pinfunction "3_3") (pintype "bidirectional"))
      (node (ref "J6") (pin "1") (pinfunction "1_1") (pintype "passive"))
      (node (ref "R10") (pin "1") (pinfunction "1_1") (pintype "passive"))
      (node (ref "R29") (pin "1") (pinfunction "1_1") (pintype "passive"))
      (node (ref "R6") (pin "1") (pinfunction "1_1") (pintype "passive"))
      (node (ref "R7") (pin "1") (pinfunction "1_1") (pintype "passive"))
      (node (ref "R8") (pin "1") (pinfunction "1_1") (pintype "passive"))
      (node (ref "R9") (pin "1") (pinfunction "1_1") (pintype "passive"))
      (node (ref "U1") (pin "10") (pinfunction "AVSS_RFN_10") (pintype "bidirectional"))
      (node (ref "U1") (pin "11") (pinfunction "TST_11") (pintype "bidirectional"))
      (node (ref "U1") (pin "20") (pinfunction "DVSS_20") (pintype "bidirectional"))
      (node (ref "U1") (pin "24") (pinfunction "DVSS_24") (pintype "bidirectional"))
      (node (ref "U1") (pin "33") (pinfunction "CLKI_33") (pintype "bidirectional"))
      (node (ref "U1") (pin "35") (pinfunction "DVSS_35") (pintype "bidirectional"))
      (node (ref "U1") (pin "45") (pinfunction "DVSS_45") (pintype "bidirectional"))
      (node (ref "U1") (pin "55") (pinfunction "DVSS_55") (pintype "bidirectional"))
      (node (ref "U1") (pin "58") (pinfunction "AVSS_58") (pintype "bidirectional"))
      (node (ref "U1") (pin "61") (pinfunction "AVSS_61") (pintype "bidirectional"))
      (node (ref "U1") (pin "7") (pinfunction "AVSS_RFP_7") (pintype "bidirectional"))
      (node (ref "U2") (pin "GND@1") (pinfunction "GND_GND@1") (pintype "bidirectional"))
      (node (ref "U2") (pin "GND@2") (pinfunction "GND_GND@2") (pintype "bidirectional"))
      (node (ref "U2") (pin "RES@1") (pinfunction "GND_RES@1") (pintype "bidirectional"))
      (node (ref "U2") (pin "RES@2") (pinfunction "GND_RES@2") (pintype "bidirectional"))
      (node (ref "U2") (pin "RES@3") (pinfunction "GND_RES@3") (pintype "bidirectional"))
      (node (ref "U2") (pin "RES@4") (pinfunction "GND_RES@4") (pintype "bidirectional"))
      (node (ref "U2") (pin "RES@5") (pinfunction "GND_RES@5") (pintype "bidirectional"))
      (node (ref "U7") (pin "2") (pinfunction "GND_2") (pintype "input"))
      (node (ref "U8") (pin "P2") (pinfunction "P2_P2") (pintype "bidirectional"))
    )
    (net (code "10") (name "MISO") (class "Default")
      (node (ref "J1") (pin "1") (pinfunction "1_1") (pintype "passive"))
      (node (ref "U1") (pin "39") (pinfunction "PB3(MISO/PDO/PCINT3)_39") (pintype "bidirectional"))
    )
    (net (code "11") (name "MOSI") (class "Default")
      (node (ref "J1") (pin "4") (pinfunction "4_4") (pintype "passive"))
      (node (ref "U1") (pin "38") (pinfunction "PB2(MOSI/PDI/PCINT2)_38") (pintype "bidirectional"))
    )
    (net (code "12") (name "Net-(A8-SIGNAL)") (class "Default")
      (node (ref "A8") (pin "FEED") (pinfunction "SIGNAL_FEED") (pintype "bidirectional"))
      (node (ref "B1") (pin "1") (pinfunction "IN_1") (pintype "bidirectional"))
      (node (ref "C4") (pin "1") (pinfunction "1_1") (pintype "passive"))
    )
    (net (code "13") (name "Net-(B1-GND-Pad2)") (class "Default")
      (node (ref "B1") (pin "2") (pinfunction "GND_2") (pintype "bidirectional"))
      (node (ref "C3") (pin "2") (pinfunction "2_2") (pintype "passive"))
    )
    (net (code "14") (name "Net-(B1-OUT1)") (class "Default")
      (node (ref "B1") (pin "4") (pinfunction "OUT1_4") (pintype "bidirectional"))
      (node (ref "U1") (pin "8") (pinfunction "RFP_8") (pintype "bidirectional"))
    )
    (net (code "15") (name "Net-(B1-OUT2)") (class "Default")
      (node (ref "B1") (pin "3") (pinfunction "OUT2_3") (pintype "bidirectional"))
      (node (ref "U1") (pin "9") (pinfunction "RFN_9") (pintype "bidirectional"))
    )
    (net (code "16") (name "Net-(B2-P)") (class "Default")
      (node (ref "B2") (pin "2") (pinfunction "P_2") (pintype "bidirectional"))
      (node (ref "J2") (pin "1") (pinfunction "1_1") (pintype "passive"))
    )
    (net (code "17") (name "Net-(C7-Pad1)") (class "Default")
      (node (ref "C7") (pin "1") (pinfunction "1_1") (pintype "passive"))
      (node (ref "U1") (pin "21") (pinfunction "DVDD_21") (pintype "bidirectional"))
      (node (ref "U1") (pin "22") (pinfunction "DVDD_22") (pintype "bidirectional"))
    )
    (net (code "18") (name "Net-(C13-Pad1)") (class "Default")
      (node (ref "C13") (pin "1") (pinfunction "1_1") (pintype "passive"))
      (node (ref "U2") (pin "C1") (pinfunction "C1_C1") (pintype "bidirectional"))
    )
    (net (code "19") (name "Net-(C14-Pad1)") (class "Default")
      (node (ref "C14") (pin "1") (pinfunction "1_1") (pintype "passive"))
      (node (ref "U2") (pin "CAP") (pinfunction "CAP_CAP") (pintype "bidirectional"))
    )
    (net (code "20") (name "Net-(C22-Pad1)") (class "Default")
      (node (ref "C22") (pin "1") (pinfunction "1_1") (pintype "passive"))
      (node (ref "J6") (pin "2") (pinfunction "2_2") (pintype "passive"))
    )
    (net (code "21") (name "Net-(D1-PadA)") (class "Default")
      (node (ref "D1") (pin "A") (pinfunction "A_A") (pintype "passive"))
      (node (ref "R2") (pin "1") (pinfunction "1_1") (pintype "passive"))
    )
    (net (code "22") (name "Net-(D2-PadA)") (class "Default")
      (node (ref "D2") (pin "A") (pinfunction "A_A") (pintype "passive"))
      (node (ref "R3") (pin "1") (pinfunction "1_1") (pintype "passive"))
    )
    (net (code "23") (name "Net-(D8-PadA)") (class "Default")
      (node (ref "D8") (pin "A") (pinfunction "A_A") (pintype "passive"))
      (node (ref "R11") (pin "1") (pinfunction "1_1") (pintype "passive"))
    )
    (net (code "24") (name "Net-(D9-PadA)") (class "Default")
      (node (ref "D9") (pin "A") (pinfunction "A_A") (pintype "passive"))
      (node (ref "R12") (pin "1") (pinfunction "1_1") (pintype "passive"))
    )
    (net (code "25") (name "Net-(D10-PadA)") (class "Default")
      (node (ref "D10") (pin "A") (pinfunction "A_A") (pintype "passive"))
      (node (ref "R14") (pin "1") (pinfunction "1_1") (pintype "passive"))
    )
    (net (code "26") (name "Net-(D10-PadC)") (class "Default")
      (node (ref "D10") (pin "C") (pinfunction "C_C") (pintype "passive"))
      (node (ref "D11") (pin "C") (pinfunction "C_C") (pintype "passive"))
      (node (ref "D12") (pin "C") (pinfunction "C_C") (pintype "passive"))
      (node (ref "D17") (pin "C") (pinfunction "C_C") (pintype "passive"))
      (node (ref "D19") (pin "C") (pinfunction "C_C") (pintype "passive"))
      (node (ref "D20") (pin "C") (pinfunction "C_C") (pintype "passive"))
      (node (ref "D22") (pin "C") (pinfunction "C_C") (pintype "passive"))
      (node (ref "D24") (pin "C") (pinfunction "C_C") (pintype "passive"))
      (node (ref "D8") (pin "C") (pinfunction "C_C") (pintype "passive"))
      (node (ref "D9") (pin "C") (pinfunction "C_C") (pintype "passive"))
      (node (ref "Q5") (pin "D") (pinfunction "D_D") (pintype "bidirectional"))
    )
    (net (code "27") (name "Net-(D11-PadA)") (class "Default")
      (node (ref "D11") (pin "A") (pinfunction "A_A") (pintype "passive"))
      (node (ref "R15") (pin "1") (pinfunction "1_1") (pintype "passive"))
    )
    (net (code "28") (name "Net-(D12-PadA)") (class "Default")
      (node (ref "D12") (pin "A") (pinfunction "A_A") (pintype "passive"))
      (node (ref "R16") (pin "1") (pinfunction "1_1") (pintype "passive"))
    )
    (net (code "29") (name "Net-(D13-PadA)") (class "Default")
      (node (ref "D13") (pin "A") (pinfunction "A_A") (pintype "passive"))
      (node (ref "R17") (pin "1") (pinfunction "1_1") (pintype "passive"))
    )
    (net (code "30") (name "Net-(D13-PadC)") (class "Default")
      (node (ref "D13") (pin "C") (pinfunction "C_C") (pintype "passive"))
      (node (ref "D14") (pin "C") (pinfunction "C_C") (pintype "passive"))
      (node (ref "D15") (pin "C") (pinfunction "C_C") (pintype "passive"))
      (node (ref "D16") (pin "C") (pinfunction "C_C") (pintype "passive"))
      (node (ref "D18") (pin "C") (pinfunction "C_C") (pintype "passive"))
      (node (ref "D21") (pin "C") (pinfunction "C_C") (pintype "passive"))
      (node (ref "D23") (pin "C") (pinfunction "C_C") (pintype "passive"))
      (node (ref "D25") (pin "C") (pinfunction "C_C") (pintype "passive"))
      (node (ref "Q6") (pin "D") (pinfunction "D_D") (pintype "bidirectional"))
    )
    (net (code "31") (name "Net-(D14-PadA)") (class "Default")
      (node (ref "D14") (pin "A") (pinfunction "A_A") (pintype "passive"))
      (node (ref "R18") (pin "1") (pinfunction "1_1") (pintype "passive"))
    )
    (net (code "32") (name "Net-(D15-PadA)") (class "Default")
      (node (ref "D15") (pin "A") (pinfunction "A_A") (pintype "passive"))
      (node (ref "R19") (pin "1") (pinfunction "1_1") (pintype "passive"))
    )
    (net (code "33") (name "Net-(D16-PadA)") (class "Default")
      (node (ref "D16") (pin "A") (pinfunction "A_A") (pintype "passive"))
      (node (ref "R20") (pin "1") (pinfunction "1_1") (pintype "passive"))
    )
    (net (code "34") (name "Net-(D17-PadA)") (class "Default")
      (node (ref "D17") (pin "A") (pinfunction "A_A") (pintype "passive"))
      (node (ref "R21") (pin "1") (pinfunction "1_1") (pintype "passive"))
    )
    (net (code "35") (name "Net-(D18-PadA)") (class "Default")
      (node (ref "D18") (pin "A") (pinfunction "A_A") (pintype "passive"))
      (node (ref "R22") (pin "1") (pinfunction "1_1") (pintype "passive"))
    )
    (net (code "36") (name "Net-(D19-PadA)") (class "Default")
      (node (ref "D19") (pin "A") (pinfunction "A_A") (pintype "passive"))
      (node (ref "R23") (pin "1") (pinfunction "1_1") (pintype "passive"))
    )
    (net (code "37") (name "Net-(D20-PadA)") (class "Default")
      (node (ref "D20") (pin "A") (pinfunction "A_A") (pintype "passive"))
      (node (ref "R24") (pin "1") (pinfunction "1_1") (pintype "passive"))
    )
    (net (code "38") (name "Net-(D21-PadA)") (class "Default")
      (node (ref "D21") (pin "A") (pinfunction "A_A") (pintype "passive"))
      (node (ref "R28") (pin "1") (pinfunction "1_1") (pintype "passive"))
    )
    (net (code "39") (name "Net-(D22-PadA)") (class "Default")
      (node (ref "D22") (pin "A") (pinfunction "A_A") (pintype "passive"))
      (node (ref "R13") (pin "1") (pinfunction "1_1") (pintype "passive"))
    )
    (net (code "40") (name "Net-(D23-PadA)") (class "Default")
      (node (ref "D23") (pin "A") (pinfunction "A_A") (pintype "passive"))
      (node (ref "R25") (pin "1") (pinfunction "1_1") (pintype "passive"))
    )
    (net (code "41") (name "Net-(D24-PadA)") (class "Default")
      (node (ref "D24") (pin "A") (pinfunction "A_A") (pintype "passive"))
      (node (ref "R26") (pin "1") (pinfunction "1_1") (pintype "passive"))
    )
    (net (code "42") (name "Net-(D25-PadA)") (class "Default")
      (node (ref "D25") (pin "A") (pinfunction "A_A") (pintype "passive"))
      (node (ref "R27") (pin "1") (pinfunction "1_1") (pintype "passive"))
    )
    (net (code "43") (name "Net-(J3-1)") (class "Default")
      (node (ref "C9") (pin "1") (pinfunction "1_1") (pintype "passive"))
      (node (ref "J3") (pin "DTR") (pinfunction "1_DTR") (pintype "passive"))
    )
    (net (code "44") (name "Net-(U1-AVDD)") (class "Default")
      (node (ref "C8") (pin "1") (pinfunction "1_1") (pintype "passive"))
      (node (ref "U1") (pin "60") (pinfunction "AVDD_60") (pintype "bidirectional"))
    )
    (net (code "45") (name "Net-(U1-XTAL1)") (class "Default")
      (node (ref "C6") (pin "1") (pinfunction "1_1") (pintype "passive"))
      (node (ref "U1") (pin "57") (pinfunction "XTAL1_57") (pintype "bidirectional"))
      (node (ref "Y1") (pin "3") (pinfunction "2_3") (pintype "passive"))
    )
    (net (code "46") (name "Net-(U1-XTAL2)") (class "Default")
      (node (ref "C5") (pin "1") (pinfunction "1_1") (pintype "passive"))
      (node (ref "U1") (pin "56") (pinfunction "XTAL2_56") (pintype "bidirectional"))
      (node (ref "Y1") (pin "1") (pinfunction "1_1") (pintype "passive"))
    )
    (net (code "47") (name "Net-(U3-V-)") (class "Default")
      (node (ref "D3") (pin "A") (pinfunction "A_A") (pintype "passive"))
      (node (ref "Q1") (pin "D") (pinfunction "D_D") (pintype "bidirectional"))
      (node (ref "U3") (pin "2") (pinfunction "V-_2") (pintype "bidirectional"))
    )
    (net (code "48") (name "Net-(U4-V-)") (class "Default")
      (node (ref "D4") (pin "A") (pinfunction "A_A") (pintype "passive"))
      (node (ref "Q2") (pin "D") (pinfunction "D_D") (pintype "bidirectional"))
      (node (ref "U4") (pin "2") (pinfunction "V-_2") (pintype "bidirectional"))
    )
    (net (code "49") (name "Net-(U5-V-)") (class "Default")
      (node (ref "D5") (pin "A") (pinfunction "A_A") (pintype "passive"))
      (node (ref "Q3") (pin "D") (pinfunction "D_D") (pintype "bidirectional"))
      (node (ref "U5") (pin "2") (pinfunction "V-_2") (pintype "bidirectional"))
    )
    (net (code "50") (name "Net-(U6-V-)") (class "Default")
      (node (ref "D6") (pin "A") (pinfunction "A_A") (pintype "passive"))
      (node (ref "Q4") (pin "D") (pinfunction "D_D") (pintype "bidirectional"))
      (node (ref "U6") (pin "2") (pinfunction "V-_2") (pintype "bidirectional"))
    )
    (net (code "51") (name "PG0") (class "Default")
      (node (ref "R2") (pin "2") (pinfunction "2_2") (pintype "passive"))
      (node (ref "U1") (pin "14") (pinfunction "PG0(DIG3)_14") (pintype "bidirectional"))
    )
    (net (code "52") (name "PG1") (class "Default")
      (node (ref "R3") (pin "2") (pinfunction "2_2") (pintype "passive"))
      (node (ref "U1") (pin "15") (pinfunction "PG1(DIG1)_15") (pintype "bidirectional"))
    )
    (net (code "53") (name "RESET") (class "Default")
      (node (ref "B3") (pin "1") (pinfunction "1_1") (pintype "passive"))
      (node (ref "B3") (pin "2") (pinfunction "1_2") (pintype "passive"))
      (node (ref "C22") (pin "2") (pinfunction "2_2") (pintype "passive"))
      (node (ref "C9") (pin "2") (pinfunction "2_2") (pintype "passive"))
      (node (ref "J1") (pin "5") (pinfunction "5_5") (pintype "passive"))
      (node (ref "R1") (pin "1") (pinfunction "1_1") (pintype "passive"))
      (node (ref "U1") (pin "12") (pinfunction "RSTN_12") (pintype "bidirectional"))
    )
    (net (code "54") (name "RX0") (class "Default")
      (node (ref "J3") (pin "TXO") (pinfunction "3_TXO") (pintype "passive"))
      (node (ref "J7") (pin "1") (pinfunction "1_1") (pintype "passive"))
      (node (ref "U1") (pin "46") (pinfunction "PE0(RXD0/PCINT8)_46") (pintype "bidirectional"))
    )
    (net (code "55") (name "SCK") (class "Default")
      (node (ref "J1") (pin "3") (pinfunction "3_3") (pintype "passive"))
      (node (ref "U1") (pin "37") (pinfunction "PB1(SCK/PCINT1)_37") (pintype "bidirectional"))
    )
    (net (code "56") (name "SCL") (class "Default")
      (node (ref "J4") (pin "3") (pinfunction "3_3") (pintype "passive"))
      (node (ref "J5") (pin "2") (pinfunction "2_2") (pintype "bidirectional"))
      (node (ref "R5") (pin "1") (pinfunction "1_1") (pintype "passive"))
      (node (ref "U1") (pin "25") (pinfunction "PD0(SCL/INT0)_25") (pintype "bidirectional"))
      (node (ref "U2") (pin "SCL/SPC") (pinfunction "SCL/SPC_SCL/SPC") (pintype "bidirectional"))
    )
    (net (code "57") (name "SDA") (class "Default")
      (node (ref "J4") (pin "4") (pinfunction "4_4") (pintype "passive"))
      (node (ref "J5") (pin "1") (pinfunction "1_1") (pintype "bidirectional"))
      (node (ref "R4") (pin "1") (pinfunction "1_1") (pintype "passive"))
      (node (ref "U1") (pin "26") (pinfunction "PD1(SDA/INT1)_26") (pintype "bidirectional"))
      (node (ref "U2") (pin "SDA/SDI/SDO") (pinfunction "SDA/SDI/SDO_SDA/SDI/SDO") (pintype "bidirectional"))
    )
    (net (code "58") (name "TX0") (class "Default")
      (node (ref "J3") (pin "RXI") (pinfunction "2_RXI") (pintype "passive"))
      (node (ref "J7") (pin "2") (pinfunction "2_2") (pintype "passive"))
      (node (ref "U1") (pin "47") (pinfunction "PE1(TXD0)_47") (pintype "bidirectional"))
    )
    (net (code "59") (name "VBAT") (class "Default")
      (node (ref "C15") (pin "1") (pinfunction "+_1") (pintype "passive"))
      (node (ref "C16") (pin "1") (pinfunction "+_1") (pintype "passive"))
      (node (ref "C17") (pin "1") (pinfunction "+_1") (pintype "passive"))
      (node (ref "C18") (pin "1") (pinfunction "+_1") (pintype "passive"))
      (node (ref "C20") (pin "2") (pinfunction "2_2") (pintype "passive"))
      (node (ref "D3") (pin "C") (pinfunction "C_C") (pintype "passive"))
      (node (ref "D4") (pin "C") (pinfunction "C_C") (pintype "passive"))
      (node (ref "D5") (pin "C") (pinfunction "C_C") (pintype "passive"))
      (node (ref "D6") (pin "C") (pinfunction "C_C") (pintype "passive"))
      (node (ref "J2") (pin "2") (pinfunction "2_2") (pintype "passive"))
      (node (ref "J4") (pin "10") (pinfunction "10_10") (pintype "passive"))
      (node (ref "R11") (pin "2") (pinfunction "2_2") (pintype "passive"))
      (node (ref "R12") (pin "2") (pinfunction "2_2") (pintype "passive"))
      (node (ref "R13") (pin "2") (pinfunction "2_2") (pintype "passive"))
      (node (ref "R14") (pin "2") (pinfunction "2_2") (pintype "passive"))
      (node (ref "R15") (pin "2") (pinfunction "2_2") (pintype "passive"))
      (node (ref "R16") (pin "2") (pinfunction "2_2") (pintype "passive"))
      (node (ref "R17") (pin "2") (pinfunction "2_2") (pintype "passive"))
      (node (ref "R18") (pin "2") (pinfunction "2_2") (pintype "passive"))
      (node (ref "R19") (pin "2") (pinfunction "2_2") (pintype "passive"))
      (node (ref "R20") (pin "2") (pinfunction "2_2") (pintype "passive"))
      (node (ref "R21") (pin "2") (pinfunction "2_2") (pintype "passive"))
      (node (ref "R22") (pin "2") (pinfunction "2_2") (pintype "passive"))
      (node (ref "R23") (pin "2") (pinfunction "2_2") (pintype "passive"))
      (node (ref "R24") (pin "2") (pinfunction "2_2") (pintype "passive"))
      (node (ref "R25") (pin "2") (pinfunction "2_2") (pintype "passive"))
      (node (ref "R26") (pin "2") (pinfunction "2_2") (pintype "passive"))
      (node (ref "R27") (pin "2") (pinfunction "2_2") (pintype "passive"))
      (node (ref "R28") (pin "2") (pinfunction "2_2") (pintype "passive"))
      (node (ref "U3") (pin "1") (pinfunction "V+_1") (pintype "bidirectional"))
      (node (ref "U4") (pin "1") (pinfunction "V+_1") (pintype "bidirectional"))
      (node (ref "U5") (pin "1") (pinfunction "V+_1") (pintype "bidirectional"))
      (node (ref "U6") (pin "1") (pinfunction "V+_1") (pintype "bidirectional"))
      (node (ref "U7") (pin "1") (pinfunction "IN_1") (pintype "input"))
      (node (ref "U7") (pin "3") (pinfunction "EN_3") (pintype "input"))
    )
    (net (code "60") (name "unconnected-(J1-Pad2)") (class "Default")
      (node (ref "J1") (pin "2") (pinfunction "2_2") (pintype "passive"))
    )
    (net (code "61") (name "unconnected-(J3-5-PadCTS)") (class "Default")
      (node (ref "J3") (pin "CTS") (pinfunction "5_CTS") (pintype "passive"))
    )
    (net (code "62") (name "unconnected-(U1-AREF-Pad62)") (class "Default")
      (node (ref "U1") (pin "62") (pinfunction "AREF_62") (pintype "bidirectional"))
    )
    (net (code "63") (name "unconnected-(U1-PB0(SSN{slash}PCINT0)-Pad36)") (class "Default")
      (node (ref "U1") (pin "36") (pinfunction "PB0(SSN/PCINT0)_36") (pintype "bidirectional"))
    )
    (net (code "64") (name "unconnected-(U1-PB7(OC0A{slash}OC1C{slash}PCINT7)-Pad43)") (class "Default")
      (node (ref "U1") (pin "43") (pinfunction "PB7(OC0A/OC1C/PCINT7)_43") (pintype "bidirectional"))
    )
    (net (code "65") (name "unconnected-(U1-PD2(RXD1{slash}INT2)-Pad27)") (class "Default")
      (node (ref "U1") (pin "27") (pinfunction "PD2(RXD1/INT2)_27") (pintype "bidirectional"))
    )
    (net (code "66") (name "unconnected-(U1-PD3(TXD1{slash}INT3)-Pad28)") (class "Default")
      (node (ref "U1") (pin "28") (pinfunction "PD3(TXD1/INT3)_28") (pintype "bidirectional"))
    )
    (net (code "67") (name "unconnected-(U1-PD4(ICP1)-Pad29)") (class "Default")
      (node (ref "U1") (pin "29") (pinfunction "PD4(ICP1)_29") (pintype "bidirectional"))
    )
    (net (code "68") (name "unconnected-(U1-PD5(XCK1)-Pad30)") (class "Default")
      (node (ref "U1") (pin "30") (pinfunction "PD5(XCK1)_30") (pintype "bidirectional"))
    )
    (net (code "69") (name "unconnected-(U1-PD6(T1)-Pad31)") (class "Default")
      (node (ref "U1") (pin "31") (pinfunction "PD6(T1)_31") (pintype "bidirectional"))
    )
    (net (code "70") (name "unconnected-(U1-PD7(T0)-Pad32)") (class "Default")
      (node (ref "U1") (pin "32") (pinfunction "PD7(T0)_32") (pintype "bidirectional"))
    )
    (net (code "71") (name "unconnected-(U1-PE2(XCK0{slash}AIN0)-Pad48)") (class "Default")
      (node (ref "U1") (pin "48") (pinfunction "PE2(XCK0/AIN0)_48") (pintype "bidirectional"))
    )
    (net (code "72") (name "unconnected-(U1-PE6(T3{slash}INT6)-Pad52)") (class "Default")
      (node (ref "U1") (pin "52") (pinfunction "PE6(T3/INT6)_52") (pintype "bidirectional"))
    )
    (net (code "73") (name "unconnected-(U1-PE7(ICP3{slash}INT7{slash}CLKO)-Pad53)") (class "Default")
      (node (ref "U1") (pin "53") (pinfunction "PE7(ICP3/INT7/CLKO)_53") (pintype "bidirectional"))
    )
    (net (code "74") (name "unconnected-(U1-PF0(ADC0)-Pad63)") (class "Default")
      (node (ref "U1") (pin "63") (pinfunction "PF0(ADC0)_63") (pintype "bidirectional"))
    )
    (net (code "75") (name "unconnected-(U1-PF1(ADC1)-Pad64)") (class "Default")
      (node (ref "U1") (pin "64") (pinfunction "PF1(ADC1)_64") (pintype "bidirectional"))
    )
    (net (code "76") (name "unconnected-(U1-PF2(ADC2{slash}DIG2)-Pad1)") (class "Default")
      (node (ref "U1") (pin "1") (pinfunction "PF2(ADC2/DIG2)_1") (pintype "bidirectional"))
    )
    (net (code "77") (name "unconnected-(U1-PF3(ADC3{slash}DIG4)-Pad2)") (class "Default")
      (node (ref "U1") (pin "2") (pinfunction "PF3(ADC3/DIG4)_2") (pintype "bidirectional"))
    )
    (net (code "78") (name "unconnected-(U1-PF4(ADC4{slash}TCK)-Pad3)") (class "Default")
      (node (ref "U1") (pin "3") (pinfunction "PF4(ADC4/TCK)_3") (pintype "bidirectional"))
    )
    (net (code "79") (name "unconnected-(U1-PF5(ADC5{slash}TMS)-Pad4)") (class "Default")
      (node (ref "U1") (pin "4") (pinfunction "PF5(ADC5/TMS)_4") (pintype "bidirectional"))
    )
    (net (code "80") (name "unconnected-(U1-PF6(ADC6{slash}TDO)-Pad5)") (class "Default")
      (node (ref "U1") (pin "5") (pinfunction "PF6(ADC6/TDO)_5") (pintype "bidirectional"))
    )
    (net (code "81") (name "unconnected-(U1-PF7(ADC7{slash}TDI)-Pad6)") (class "Default")
      (node (ref "U1") (pin "6") (pinfunction "PF7(ADC7/TDI)_6") (pintype "bidirectional"))
    )
    (net (code "82") (name "unconnected-(U1-PG2(AMR)-Pad16)") (class "Default")
      (node (ref "U1") (pin "16") (pinfunction "PG2(AMR)_16") (pintype "bidirectional"))
    )
    (net (code "83") (name "unconnected-(U1-PG3(TOSC2)-Pad17)") (class "Default")
      (node (ref "U1") (pin "17") (pinfunction "PG3(TOSC2)_17") (pintype "bidirectional"))
    )
    (net (code "84") (name "unconnected-(U1-PG4(TOSC1)-Pad18)") (class "Default")
      (node (ref "U1") (pin "18") (pinfunction "PG4(TOSC1)_18") (pintype "bidirectional"))
    )
    (net (code "85") (name "unconnected-(U1-PG5(OC0B)-Pad19)") (class "Default")
      (node (ref "U1") (pin "19") (pinfunction "PG5(OC0B)_19") (pintype "bidirectional"))
    )
    (net (code "86") (name "unconnected-(U1-RSTON-Pad13)") (class "Default")
      (node (ref "U1") (pin "13") (pinfunction "RSTON_13") (pintype "bidirectional"))
    )
    (net (code "87") (name "unconnected-(U2-PadDRDY_M)") (class "Default")
      (node (ref "U2") (pin "DRDY_M") (pinfunction "DRDY_M_DRDY_M") (pintype "bidirectional"))
    )
    (net (code "88") (name "unconnected-(U2-PadINT1_A{slash}G)") (class "Default")
      (node (ref "U2") (pin "INT1_A/G") (pinfunction "INT1_A/G_INT1_A/G") (pintype "bidirectional"))
    )
    (net (code "89") (name "unconnected-(U2-PadINT2_A{slash}G)") (class "Default")
      (node (ref "U2") (pin "INT2_A/G") (pinfunction "INT2_A/G_INT2_A/G") (pintype "bidirectional"))
    )
    (net (code "90") (name "unconnected-(U2-PadINT_M)") (class "Default")
      (node (ref "U2") (pin "INT_M") (pinfunction "INT_M_INT_M") (pintype "bidirectional"))
    )
    (net (code "91") (name "unconnected-(U7-NC{slash}FB-Pad4)") (class "Default")
      (node (ref "U7") (pin "4") (pinfunction "NC/FB_4") (pintype "passive"))
    )
  )
)
